# MCU.net
KiCad netlist of a schematic drawn in Altium Designer
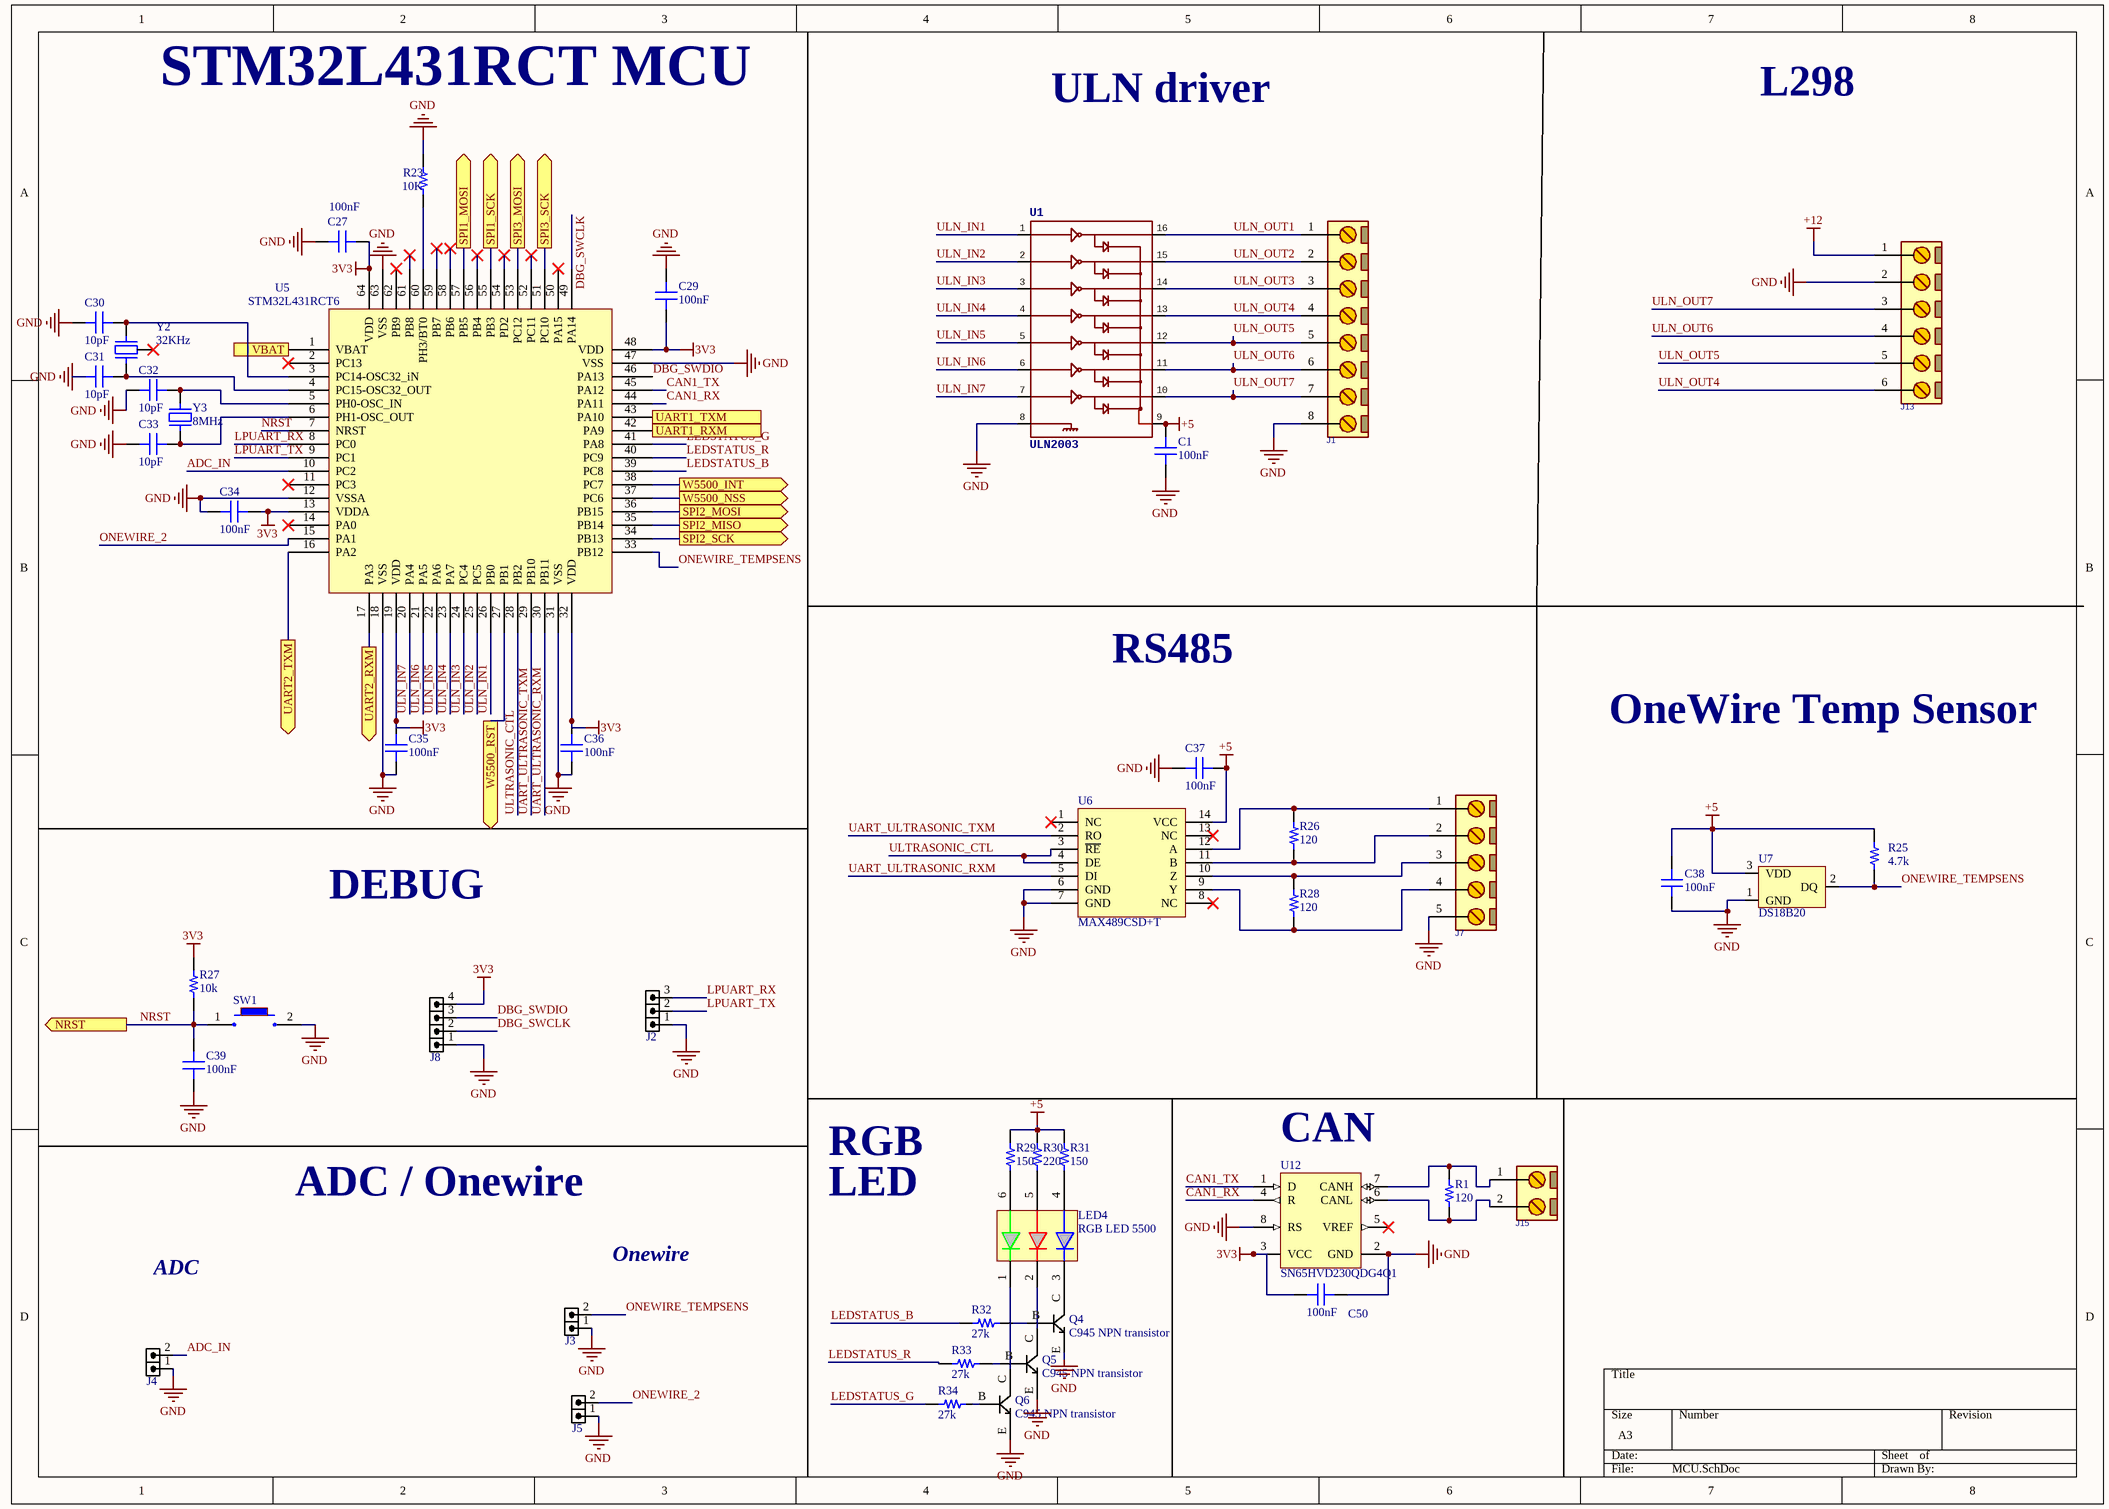
[diagram p0: MCU.SchDoc]

(export (version "E")
  (design (tool "Eeschema 10.0.6"))
  (components
    (comp (ref "C1")
      (value "100nF")
      (footprint "CAP 0805_2012")
      (description "SMT Capacitor")
      (libsource (lib "Capacitor") (part "Cap 0805"))
    )
    (comp (ref "C27")
      (value "100nF")
      (footprint "CAP 0805_2012")
      (description "SMT Capacitor")
      (libsource (lib "Capacitor") (part "Cap 0805"))
    )
    (comp (ref "C29")
      (value "100nF")
      (footprint "CAP 0805_2012")
      (description "SMT Capacitor")
      (libsource (lib "Capacitor") (part "Cap 0805"))
    )
    (comp (ref "C30")
      (value "10pF")
      (footprint "CAP 0805_2012")
      (description "SMT Capacitor")
      (libsource (lib "Capacitor") (part "Cap 0805"))
    )
    (comp (ref "C31")
      (value "10pF")
      (footprint "CAP 0805_2012")
      (description "SMT Capacitor")
      (libsource (lib "Capacitor") (part "Cap 0805"))
    )
    (comp (ref "C32")
      (value "10pF")
      (footprint "CAP 0805_2012")
      (description "SMT Capacitor")
      (libsource (lib "Capacitor") (part "Cap 0805"))
    )
    (comp (ref "C33")
      (value "10pF")
      (footprint "CAP 0805_2012")
      (description "SMT Capacitor")
      (libsource (lib "Capacitor") (part "Cap 0805"))
    )
    (comp (ref "C34")
      (value "100nF")
      (footprint "CAP 0805_2012")
      (description "SMT Capacitor")
      (libsource (lib "Capacitor") (part "Cap 0805"))
    )
    (comp (ref "C35")
      (value "100nF")
      (footprint "CAP 0805_2012")
      (description "SMT Capacitor")
      (libsource (lib "Capacitor") (part "Cap 0805"))
    )
    (comp (ref "C36")
      (value "100nF")
      (footprint "CAP 0805_2012")
      (description "SMT Capacitor")
      (libsource (lib "Capacitor") (part "Cap 0805"))
    )
    (comp (ref "C37")
      (value "100nF")
      (footprint "CAP 0805_2012")
      (description "SMT Capacitor")
      (libsource (lib "Capacitor") (part "Cap 0805"))
    )
    (comp (ref "C38")
      (value "100nF")
      (footprint "CAP 0805_2012")
      (description "SMT Capacitor")
      (libsource (lib "Capacitor") (part "Cap 0805"))
    )
    (comp (ref "C39")
      (value "100nF")
      (footprint "CAP 0805_2012")
      (description "SMT Capacitor")
      (libsource (lib "Capacitor") (part "Cap 0805"))
    )
    (comp (ref "C50")
      (value "100nF")
      (footprint "CAP 0805_2012")
      (description "SMT Capacitor")
      (libsource (lib "Capacitor") (part "Cap 0805"))
    )
    (comp (ref "J1")
      (value "Phoenix MSTBV 8Pin")
      (footprint "PHOENIX MSTBV_8")
      (description "CONN, PHOENIX MSTBV, 5-G, 5.08mm pitch")
      (fields (field (name "PARTNUMBER") "MSTBV 2,5/ 8-G-5,08 1758076"))
      (libsource (lib "Conn Terminal") (part "Phoenix MSTBV 8Pin"))
    )
    (comp (ref "J2")
      (value "HDRM3")
      (footprint "HDR_M_1X3")
      (description "CONN, HEADER, Male, pitch: 2.54mm, 3POS")
      (libsource (lib "Conn Header") (part "HDR_M_1X3"))
    )
    (comp (ref "J3")
      (value "HDRM2")
      (footprint "HDR_M_1X2")
      (description "CONN, HEADER, Male, pitch: 2.54mm, 2POS")
      (libsource (lib "Conn Header") (part "HDR_M_1X2"))
    )
    (comp (ref "J4")
      (value "HDRM2")
      (footprint "HDR_M_1X2")
      (description "CONN, HEADER, Male, pitch: 2.54mm, 2POS")
      (libsource (lib "Conn Header") (part "HDR_M_1X2"))
    )
    (comp (ref "J5")
      (value "HDRM2")
      (footprint "HDR_M_1X2")
      (description "CONN, HEADER, Male, pitch: 2.54mm, 2POS")
      (libsource (lib "Conn Header") (part "HDR_M_1X2"))
    )
    (comp (ref "J7")
      (value "Phoenix MSTBV 5Pin")
      (footprint "PHOENIX MSTBV_5")
      (description "CONN, PHOENIX MSTBV, 5-G, 5.08mm pitch")
      (fields (field (name "PARTNUMBER") "MSTBV 2,5/ 5-G-5,08 1758047"))
      (libsource (lib "Conn Terminal") (part "Phoenix MSTBV 5Pin"))
    )
    (comp (ref "J8")
      (value "HDR1X4")
      (footprint "HDR_M_1X4")
      (description "CONN, HEADER, Male, pitch: 2.54mm, 4POS")
      (libsource (lib "Conn Header") (part "HDR_M_1X4"))
    )
    (comp (ref "J13")
      (value "Phoenix MKDS 6Pin")
      (footprint "TBG_6")
      (description "CONN, PHOENIX MKDS, 5.08mm pitch")
      (fields (field (name "PARTNUMBER") "MKDS 1,5/ 6-5,08 - 1710726"))
      (libsource (lib "Conn Terminal") (part "Phoenix MKDS 6Pin"))
    )
    (comp (ref "J15")
      (value "Phoenix MSTBV 2Pin")
      (footprint "PHOENIX MSTBV_2")
      (description "CONN, PHOENIX MSTBV, 5-G, 5.08mm pitch")
      (fields (field (name "PARTNUMBER") "MSTBV 2,5/ 2-G-5,08 - 1758018"))
      (libsource (lib "Conn Terminal") (part "Phoenix MSTBV 2Pin"))
    )
    (comp (ref "LED4")
      (value "RGB LED 5500")
      (footprint "LED5500")
      (libsource (lib "AlTaLibs_MCU") (part "LED RGB 5500 Common Anode"))
    )
    (comp (ref "Q4")
      (value "C945 NPN transistor")
      (footprint "SO-23")
      (description "C945 NPN transistor hfE = 140~400")
      (libsource (lib "AlTaLibs") (part "C945"))
    )
    (comp (ref "Q5")
      (value "C945 NPN transistor")
      (footprint "SO-23")
      (description "C945 NPN transistor hfE = 140~400")
      (libsource (lib "AlTaLibs") (part "C945"))
    )
    (comp (ref "Q6")
      (value "C945 NPN transistor")
      (footprint "SO-23")
      (description "C945 NPN transistor hfE = 140~400")
      (libsource (lib "AlTaLibs") (part "C945"))
    )
    (comp (ref "R1")
      (value "120")
      (footprint "RES 0805_2012")
      (description "SMT Resistor")
      (libsource (lib "Resistor") (part "Res 0805"))
    )
    (comp (ref "R23")
      (value "10K")
      (footprint "RES 0805_2012")
      (description "SMT Resistor")
      (libsource (lib "Resistor") (part "Res 0805"))
    )
    (comp (ref "R25")
      (value "4.7k")
      (footprint "RES 0805_2012")
      (description "SMT Resistor")
      (libsource (lib "Resistor") (part "Res 0805"))
    )
    (comp (ref "R26")
      (value "120")
      (footprint "RES 0805_2012")
      (description "SMT Resistor")
      (libsource (lib "Resistor") (part "Res 0805"))
    )
    (comp (ref "R27")
      (value "10k")
      (footprint "RES 0805_2012")
      (description "SMT Resistor")
      (libsource (lib "Resistor") (part "Res 0805"))
    )
    (comp (ref "R28")
      (value "120")
      (footprint "RES 0805_2012")
      (description "SMT Resistor")
      (libsource (lib "Resistor") (part "Res 0805"))
    )
    (comp (ref "R29")
      (value "150")
      (footprint "RES 0805_2012")
      (description "SMT Resistor")
      (libsource (lib "Resistor") (part "Res 0805"))
    )
    (comp (ref "R30")
      (value "220")
      (footprint "RES 0805_2012")
      (description "SMT Resistor")
      (libsource (lib "Resistor") (part "Res 0805"))
    )
    (comp (ref "R31")
      (value "150")
      (footprint "RES 0805_2012")
      (description "SMT Resistor")
      (libsource (lib "Resistor") (part "Res 0805"))
    )
    (comp (ref "R32")
      (value "27k")
      (footprint "RES 0805_2012")
      (description "SMT Resistor")
      (libsource (lib "Resistor") (part "Res 0805"))
    )
    (comp (ref "R33")
      (value "27k")
      (footprint "RES 0805_2012")
      (description "SMT Resistor")
      (libsource (lib "Resistor") (part "Res 0805"))
    )
    (comp (ref "R34")
      (value "27k")
      (footprint "RES 0805_2012")
      (description "SMT Resistor")
      (libsource (lib "Resistor") (part "Res 0805"))
    )
    (comp (ref "SW1")
      (value "Rec. Button")
      (footprint "REC_PUSHBUTTON_FTPRNT")
      (libsource (lib "AlTaLibs") (part "Rectangle_PushButton"))
    )
    (comp (ref "U1")
      (value "ULN2003")
      (footprint "SOIC-16 9.9X3.9MM P1.27MM")
      (description "Bipolar (BJT) Transistor Array 7 NPN Darlington 50V 500mA   Surface Mount 16-SO")
      (fields (field (name "PARTNUMBER") "ULN2003D1013TR"))
      (libsource (lib "Chip") (part "ULN2003 (SMD)"))
    )
    (comp (ref "U5")
      (value "STM32L431RCT6")
      (footprint "LQFP64")
      (description "IC MCU 32BIT 256KB FLASH 64LQFP")
      (fields (field (name "MANUFACTURER") "STMicroelectronics"))
      (libsource (lib "AlTaLibs") (part "STM32L431RCT6"))
    )
    (comp (ref "U6")
      (value "MAX489CSD+T")
      (footprint "SOIC-14")
      (description "MAX489 Series 0.25 Mbps 12V Full Duplex SMT RS 485 Transceiver - SOIC-14")
      (fields (field (name "MANUFACTURER") "Maxim"))
      (libsource (lib "AlTaLibs") (part "MAX489CSD+T"))
    )
    (comp (ref "U7")
      (value "DS18B20")
      (footprint "TO-92A")
      (description "Temperature Sensor Digital, Local -55°C ~ 125°C 12 b TO-92-3")
      (fields (field (name "PARTNUMBER") "DS18B20+T&R"))
      (libsource (lib "Chip") (part "DS18B20 (THD)"))
    )
    (comp (ref "U12")
      (value "SN65HVD230QDG4Q1")
      (footprint "D8_L")
      (fields (field (name "MANUFACTURER") "Texas Instruments"))
      (libsource (lib "Texas Instruments Interface CAN") (part "SN65HVD230QDG4Q1"))
    )
    (comp (ref "Y2")
      (value "32KHz")
      (footprint "C-002R TH")
      (description "SMT Crystal")
      (libsource (lib "Xtal") (part "Crystal C-002R THD"))
    )
    (comp (ref "Y3")
      (value "8MHz")
      (footprint "HC-49S SMD")
      (description "SMT Crystal")
      (fields (field (name "PARTNUMBER") "ABLS-8.000MHZ-K4T"))
      (libsource (lib "Xtal") (part "Crystal HC-49S SMD 8MHz"))
    )
  )
  (nets
    (net (code "1") (name "+5") (class "Default")
      (node (ref "C1") (pin "2") (pinfunction "2_2") (pintype "passive"))
      (node (ref "C37") (pin "2") (pinfunction "2_2") (pintype "passive"))
      (node (ref "C38") (pin "2") (pinfunction "2_2") (pintype "passive"))
      (node (ref "R25") (pin "1") (pinfunction "1_1") (pintype "passive"))
      (node (ref "R29") (pin "2") (pinfunction "2_2") (pintype "passive"))
      (node (ref "R30") (pin "2") (pinfunction "2_2") (pintype "passive"))
      (node (ref "R31") (pin "2") (pinfunction "2_2") (pintype "passive"))
      (node (ref "U1") (pin "9") (pinfunction "9_9") (pintype "passive"))
      (node (ref "U6") (pin "14") (pinfunction "VCC_14") (pintype "passive"))
      (node (ref "U7") (pin "3") (pinfunction "VDD_3") (pintype "passive"))
    )
    (net (code "2") (name "+12") (class "Default")
      (node (ref "J13") (pin "1") (pinfunction "1_1") (pintype "passive"))
    )
    (net (code "3") (name "/ADC_IN") (class "Default")
      (node (ref "J4") (pin "2") (pinfunction "2_2") (pintype "passive"))
      (node (ref "U5") (pin "10") (pinfunction "PC2_10") (pintype "passive"))
    )
    (net (code "4") (name "/CAN1_RX") (class "Default")
      (node (ref "U12") (pin "4") (pinfunction "R_4") (pintype "output"))
      (node (ref "U5") (pin "44") (pinfunction "PA11_44") (pintype "passive"))
    )
    (net (code "5") (name "/CAN1_TX") (class "Default")
      (node (ref "U12") (pin "1") (pinfunction "D_1") (pintype "input"))
      (node (ref "U5") (pin "45") (pinfunction "PA12_45") (pintype "passive"))
    )
    (net (code "6") (name "/DBG_SWCLK") (class "Default")
      (node (ref "J8") (pin "2") (pinfunction "2_2") (pintype "passive"))
      (node (ref "U5") (pin "49") (pinfunction "PA14_49") (pintype "passive"))
    )
    (net (code "7") (name "/DBG_SWDIO") (class "Default")
      (node (ref "J8") (pin "3") (pinfunction "3_3") (pintype "passive"))
      (node (ref "U5") (pin "46") (pinfunction "PA13_46") (pintype "passive"))
    )
    (net (code "8") (name "/LEDSTATUS_B") (class "Default")
      (node (ref "R32") (pin "1") (pinfunction "1_1") (pintype "passive"))
      (node (ref "U5") (pin "39") (pinfunction "PC8_39") (pintype "passive"))
    )
    (net (code "9") (name "/LEDSTATUS_G") (class "Default")
      (node (ref "R34") (pin "1") (pinfunction "1_1") (pintype "passive"))
      (node (ref "U5") (pin "41") (pinfunction "PA8_41") (pintype "passive"))
    )
    (net (code "10") (name "/LEDSTATUS_R") (class "Default")
      (node (ref "R33") (pin "1") (pinfunction "1_1") (pintype "passive"))
      (node (ref "U5") (pin "40") (pinfunction "PC9_40") (pintype "passive"))
    )
    (net (code "11") (name "/LPUART_RX") (class "Default")
      (node (ref "J2") (pin "3") (pinfunction "3_3") (pintype "passive"))
      (node (ref "U5") (pin "8") (pinfunction "PC0_8") (pintype "passive"))
    )
    (net (code "12") (name "/LPUART_TX") (class "Default")
      (node (ref "J2") (pin "2") (pinfunction "2_2") (pintype "passive"))
      (node (ref "U5") (pin "9") (pinfunction "PC1_9") (pintype "passive"))
    )
    (net (code "13") (name "/NRST") (class "Default")
      (node (ref "C39") (pin "2") (pinfunction "2_2") (pintype "passive"))
      (node (ref "R27") (pin "1") (pinfunction "1_1") (pintype "passive"))
      (node (ref "SW1") (pin "1") (pintype "passive"))
      (node (ref "U5") (pin "7") (pinfunction "NRST_7") (pintype "passive"))
    )
    (net (code "14") (name "/ONEWIRE_2") (class "Default")
      (node (ref "J5") (pin "2") (pinfunction "2_2") (pintype "passive"))
      (node (ref "U5") (pin "15") (pinfunction "PA1_15") (pintype "passive"))
    )
    (net (code "15") (name "/ONEWIRE_TEMPSENS") (class "Default")
      (node (ref "J3") (pin "2") (pinfunction "2_2") (pintype "passive"))
      (node (ref "R25") (pin "2") (pinfunction "2_2") (pintype "passive"))
      (node (ref "U5") (pin "33") (pinfunction "PB12_33") (pintype "passive"))
      (node (ref "U7") (pin "2") (pinfunction "DQ_2") (pintype "passive"))
    )
    (net (code "16") (name "/SPI1_MOSI") (class "Default")
      (node (ref "U5") (pin "57") (pinfunction "PB5_57") (pintype "passive"))
    )
    (net (code "17") (name "/SPI1_SCK") (class "Default")
      (node (ref "U5") (pin "55") (pinfunction "PB3_55") (pintype "passive"))
    )
    (net (code "18") (name "/SPI2_MISO") (class "Default")
      (node (ref "U5") (pin "35") (pinfunction "PB14_35") (pintype "passive"))
    )
    (net (code "19") (name "/SPI2_MOSI") (class "Default")
      (node (ref "U5") (pin "36") (pinfunction "PB15_36") (pintype "passive"))
    )
    (net (code "20") (name "/SPI2_SCK") (class "Default")
      (node (ref "U5") (pin "34") (pinfunction "PB13_34") (pintype "passive"))
    )
    (net (code "21") (name "/SPI3_MOSI") (class "Default")
      (node (ref "U5") (pin "53") (pinfunction "PC12_53") (pintype "passive"))
    )
    (net (code "22") (name "/SPI3_SCK") (class "Default")
      (node (ref "U5") (pin "51") (pinfunction "PC10_51") (pintype "passive"))
    )
    (net (code "23") (name "/UART1_RXM") (class "Default")
      (node (ref "U5") (pin "42") (pinfunction "PA9_42") (pintype "passive"))
    )
    (net (code "24") (name "/UART1_TXM") (class "Default")
      (node (ref "U5") (pin "43") (pinfunction "PA10_43") (pintype "passive"))
    )
    (net (code "25") (name "/UART2_RXM") (class "Default")
      (node (ref "U5") (pin "17") (pinfunction "PA3_17") (pintype "passive"))
    )
    (net (code "26") (name "/UART2_TXM") (class "Default")
      (node (ref "U5") (pin "16") (pinfunction "PA2_16") (pintype "passive"))
    )
    (net (code "27") (name "/UART_ULTRASONIC_RXM") (class "Default")
      (node (ref "U5") (pin "30") (pinfunction "PB11_30") (pintype "passive"))
      (node (ref "U6") (pin "5") (pinfunction "DI_5") (pintype "passive"))
    )
    (net (code "28") (name "/UART_ULTRASONIC_TXM") (class "Default")
      (node (ref "U5") (pin "29") (pinfunction "PB10_29") (pintype "passive"))
      (node (ref "U6") (pin "2") (pinfunction "RO_2") (pintype "passive"))
    )
    (net (code "29") (name "/ULN_IN1") (class "Default")
      (node (ref "U1") (pin "1") (pinfunction "1_1") (pintype "passive"))
      (node (ref "U5") (pin "26") (pinfunction "PB0_26") (pintype "passive"))
    )
    (net (code "30") (name "/ULN_IN2") (class "Default")
      (node (ref "U1") (pin "2") (pinfunction "2_2") (pintype "passive"))
      (node (ref "U5") (pin "25") (pinfunction "PC5_25") (pintype "passive"))
    )
    (net (code "31") (name "/ULN_IN3") (class "Default")
      (node (ref "U1") (pin "3") (pinfunction "3_3") (pintype "passive"))
      (node (ref "U5") (pin "24") (pinfunction "PC4_24") (pintype "passive"))
    )
    (net (code "32") (name "/ULN_IN4") (class "Default")
      (node (ref "U1") (pin "4") (pinfunction "4_4") (pintype "passive"))
      (node (ref "U5") (pin "23") (pinfunction "PA7_23") (pintype "passive"))
    )
    (net (code "33") (name "/ULN_IN5") (class "Default")
      (node (ref "U1") (pin "5") (pinfunction "5_5") (pintype "passive"))
      (node (ref "U5") (pin "22") (pinfunction "PA6_22") (pintype "passive"))
    )
    (net (code "34") (name "/ULN_IN6") (class "Default")
      (node (ref "U1") (pin "6") (pinfunction "6_6") (pintype "passive"))
      (node (ref "U5") (pin "21") (pinfunction "PA5_21") (pintype "passive"))
    )
    (net (code "35") (name "/ULN_IN7") (class "Default")
      (node (ref "U1") (pin "7") (pinfunction "7_7") (pintype "passive"))
      (node (ref "U5") (pin "20") (pinfunction "PA4_20") (pintype "passive"))
    )
    (net (code "36") (name "/ULN_OUT1") (class "Default")
      (node (ref "J1") (pin "1") (pinfunction "1_1") (pintype "passive"))
      (node (ref "U1") (pin "16") (pinfunction "16_16") (pintype "passive"))
    )
    (net (code "37") (name "/ULN_OUT2") (class "Default")
      (node (ref "J1") (pin "2") (pinfunction "2_2") (pintype "passive"))
      (node (ref "U1") (pin "15") (pinfunction "15_15") (pintype "passive"))
    )
    (net (code "38") (name "/ULN_OUT3") (class "Default")
      (node (ref "J1") (pin "3") (pinfunction "3_3") (pintype "passive"))
      (node (ref "U1") (pin "14") (pinfunction "14_14") (pintype "passive"))
    )
    (net (code "39") (name "/ULN_OUT4") (class "Default")
      (node (ref "J1") (pin "4") (pinfunction "4_4") (pintype "passive"))
      (node (ref "J13") (pin "6") (pinfunction "6_6") (pintype "passive"))
      (node (ref "U1") (pin "13") (pinfunction "13_13") (pintype "passive"))
    )
    (net (code "40") (name "/ULN_OUT5") (class "Default")
      (node (ref "J1") (pin "5") (pinfunction "5_5") (pintype "passive"))
      (node (ref "J13") (pin "5") (pinfunction "5_5") (pintype "passive"))
      (node (ref "U1") (pin "12") (pinfunction "12_12") (pintype "passive"))
    )
    (net (code "41") (name "/ULN_OUT6") (class "Default")
      (node (ref "J1") (pin "6") (pinfunction "6_6") (pintype "passive"))
      (node (ref "J13") (pin "4") (pinfunction "4_4") (pintype "passive"))
      (node (ref "U1") (pin "11") (pinfunction "11_11") (pintype "passive"))
    )
    (net (code "42") (name "/ULN_OUT7") (class "Default")
      (node (ref "J1") (pin "7") (pinfunction "7_7") (pintype "passive"))
      (node (ref "J13") (pin "3") (pinfunction "3_3") (pintype "passive"))
      (node (ref "U1") (pin "10") (pinfunction "10_10") (pintype "passive"))
    )
    (net (code "43") (name "/ULTRASONIC_CTL") (class "Default")
      (node (ref "U5") (pin "28") (pinfunction "PB2_28") (pintype "passive"))
      (node (ref "U6") (pin "3") (pinfunction "~{RE}_3") (pintype "passive"))
      (node (ref "U6") (pin "4") (pinfunction "DE_4") (pintype "passive"))
    )
    (net (code "44") (name "/VBAT") (class "Default")
      (node (ref "U5") (pin "1") (pinfunction "VBAT_1") (pintype "passive"))
    )
    (net (code "45") (name "/W5500_INT") (class "Default")
      (node (ref "U5") (pin "38") (pinfunction "PC7_38") (pintype "passive"))
    )
    (net (code "46") (name "/W5500_NSS") (class "Default")
      (node (ref "U5") (pin "37") (pinfunction "PC6_37") (pintype "passive"))
    )
    (net (code "47") (name "/W5500_RST") (class "Default")
      (node (ref "U5") (pin "27") (pinfunction "PB1_27") (pintype "passive"))
    )
    (net (code "48") (name "3V3") (class "Default")
      (node (ref "C27") (pin "1") (pinfunction "1_1") (pintype "passive"))
      (node (ref "C29") (pin "1") (pinfunction "1_1") (pintype "passive"))
      (node (ref "C34") (pin "2") (pinfunction "2_2") (pintype "passive"))
      (node (ref "C35") (pin "2") (pinfunction "2_2") (pintype "passive"))
      (node (ref "C36") (pin "2") (pinfunction "2_2") (pintype "passive"))
      (node (ref "C50") (pin "2") (pinfunction "2_2") (pintype "passive"))
      (node (ref "J8") (pin "4") (pinfunction "4_4") (pintype "passive"))
      (node (ref "R27") (pin "2") (pinfunction "2_2") (pintype "passive"))
      (node (ref "U12") (pin "3") (pinfunction "VCC_3") (pintype "power_in"))
      (node (ref "U5") (pin "13") (pinfunction "VDDA_13") (pintype "passive"))
      (node (ref "U5") (pin "19") (pinfunction "VDD_19") (pintype "passive"))
      (node (ref "U5") (pin "32") (pinfunction "VDD_32") (pintype "passive"))
      (node (ref "U5") (pin "48") (pinfunction "VDD_48") (pintype "passive"))
      (node (ref "U5") (pin "64") (pinfunction "VDD_64") (pintype "passive"))
    )
    (net (code "49") (name "GND") (class "Default")
      (node (ref "C1") (pin "1") (pinfunction "1_1") (pintype "passive"))
      (node (ref "C27") (pin "2") (pinfunction "2_2") (pintype "passive"))
      (node (ref "C29") (pin "2") (pinfunction "2_2") (pintype "passive"))
      (node (ref "C30") (pin "1") (pinfunction "1_1") (pintype "passive"))
      (node (ref "C31") (pin "1") (pinfunction "1_1") (pintype "passive"))
      (node (ref "C32") (pin "1") (pinfunction "1_1") (pintype "passive"))
      (node (ref "C33") (pin "1") (pinfunction "1_1") (pintype "passive"))
      (node (ref "C34") (pin "1") (pinfunction "1_1") (pintype "passive"))
      (node (ref "C35") (pin "1") (pinfunction "1_1") (pintype "passive"))
      (node (ref "C36") (pin "1") (pinfunction "1_1") (pintype "passive"))
      (node (ref "C37") (pin "1") (pinfunction "1_1") (pintype "passive"))
      (node (ref "C38") (pin "1") (pinfunction "1_1") (pintype "passive"))
      (node (ref "C39") (pin "1") (pinfunction "1_1") (pintype "passive"))
      (node (ref "C50") (pin "1") (pinfunction "1_1") (pintype "passive"))
      (node (ref "J1") (pin "8") (pinfunction "8_8") (pintype "passive"))
      (node (ref "J13") (pin "2") (pinfunction "2_2") (pintype "passive"))
      (node (ref "J2") (pin "1") (pinfunction "1_1") (pintype "passive"))
      (node (ref "J3") (pin "1") (pinfunction "1_1") (pintype "passive"))
      (node (ref "J4") (pin "1") (pinfunction "1_1") (pintype "passive"))
      (node (ref "J5") (pin "1") (pinfunction "1_1") (pintype "passive"))
      (node (ref "J7") (pin "5") (pinfunction "5_5") (pintype "passive"))
      (node (ref "J8") (pin "1") (pinfunction "1_1") (pintype "passive"))
      (node (ref "Q4") (pin "E") (pintype "passive"))
      (node (ref "Q5") (pin "E") (pintype "passive"))
      (node (ref "Q6") (pin "E") (pintype "passive"))
      (node (ref "R23") (pin "1") (pinfunction "1_1") (pintype "passive"))
      (node (ref "SW1") (pin "2") (pintype "passive"))
      (node (ref "U1") (pin "8") (pinfunction "8_8") (pintype "passive"))
      (node (ref "U12") (pin "2") (pinfunction "GND_2") (pintype "power_in"))
      (node (ref "U12") (pin "8") (pinfunction "RS_8") (pintype "input"))
      (node (ref "U5") (pin "12") (pinfunction "VSSA_12") (pintype "passive"))
      (node (ref "U5") (pin "18") (pinfunction "VSS_18") (pintype "passive"))
      (node (ref "U5") (pin "31") (pinfunction "VSS_31") (pintype "passive"))
      (node (ref "U5") (pin "47") (pinfunction "VSS_47") (pintype "passive"))
      (node (ref "U5") (pin "63") (pinfunction "VSS_63") (pintype "passive"))
      (node (ref "U6") (pin "6") (pinfunction "GND_6") (pintype "passive"))
      (node (ref "U6") (pin "7") (pinfunction "GND_7") (pintype "passive"))
      (node (ref "U7") (pin "1") (pinfunction "GND_1") (pintype "passive"))
    )
    (net (code "50") (name "Net-(LED4-Pad1)") (class "Default")
      (node (ref "LED4") (pin "1") (pintype "passive"))
      (node (ref "Q6") (pin "C") (pintype "passive"))
    )
    (net (code "51") (name "Net-(LED4-Pad2)") (class "Default")
      (node (ref "LED4") (pin "2") (pintype "passive"))
      (node (ref "Q5") (pin "C") (pintype "passive"))
    )
    (net (code "52") (name "Net-(LED4-Pad3)") (class "Default")
      (node (ref "LED4") (pin "3") (pintype "passive"))
      (node (ref "Q4") (pin "C") (pintype "passive"))
    )
    (net (code "53") (name "Net-(LED4-Pad4)") (class "Default")
      (node (ref "LED4") (pin "4") (pintype "passive"))
      (node (ref "R31") (pin "1") (pinfunction "1_1") (pintype "passive"))
    )
    (net (code "54") (name "Net-(LED4-Pad5)") (class "Default")
      (node (ref "LED4") (pin "5") (pintype "passive"))
      (node (ref "R30") (pin "1") (pinfunction "1_1") (pintype "passive"))
    )
    (net (code "55") (name "Net-(LED4-Pad6)") (class "Default")
      (node (ref "LED4") (pin "6") (pintype "passive"))
      (node (ref "R29") (pin "1") (pinfunction "1_1") (pintype "passive"))
    )
    (net (code "56") (name "Net-(Q4-PadB)") (class "Default")
      (node (ref "Q4") (pin "B") (pintype "passive"))
      (node (ref "R32") (pin "2") (pinfunction "2_2") (pintype "passive"))
    )
    (net (code "57") (name "Net-(Q5-PadB)") (class "Default")
      (node (ref "Q5") (pin "B") (pintype "passive"))
      (node (ref "R33") (pin "2") (pinfunction "2_2") (pintype "passive"))
    )
    (net (code "58") (name "Net-(Q6-PadB)") (class "Default")
      (node (ref "Q6") (pin "B") (pintype "passive"))
      (node (ref "R34") (pin "2") (pinfunction "2_2") (pintype "passive"))
    )
    (net (code "59") (name "Net-(U5-PC14-OSC32_iN)") (class "Default")
      (node (ref "C30") (pin "2") (pinfunction "2_2") (pintype "passive"))
      (node (ref "U5") (pin "3") (pinfunction "PC14-OSC32_iN_3") (pintype "passive"))
      (node (ref "Y2") (pin "2") (pinfunction "2_2") (pintype "passive"))
    )
    (net (code "60") (name "Net-(U5-PC15-OSC32_OUT)") (class "Default")
      (node (ref "C31") (pin "2") (pinfunction "2_2") (pintype "passive"))
      (node (ref "U5") (pin "4") (pinfunction "PC15-OSC32_OUT_4") (pintype "passive"))
      (node (ref "Y2") (pin "1") (pinfunction "1_1") (pintype "passive"))
    )
    (net (code "61") (name "Net-(U5-PH0-OSC_IN)") (class "Default")
      (node (ref "C32") (pin "2") (pinfunction "2_2") (pintype "passive"))
      (node (ref "U5") (pin "5") (pinfunction "PH0-OSC_IN_5") (pintype "passive"))
      (node (ref "Y3") (pin "2") (pinfunction "2_2") (pintype "passive"))
    )
    (net (code "62") (name "Net-(U5-PH1-OSC_OUT)") (class "Default")
      (node (ref "C33") (pin "2") (pinfunction "2_2") (pintype "passive"))
      (node (ref "U5") (pin "6") (pinfunction "PH1-OSC_OUT_6") (pintype "passive"))
      (node (ref "Y3") (pin "1") (pinfunction "1_1") (pintype "passive"))
    )
    (net (code "63") (name "Net-(U5-PH3{slash}BT0)") (class "Default")
      (node (ref "R23") (pin "2") (pinfunction "2_2") (pintype "passive"))
      (node (ref "U5") (pin "60") (pinfunction "PH3/BT0_60") (pintype "passive"))
    )
    (net (code "64") (name "Net-(U6-A)") (class "Default")
      (node (ref "J7") (pin "1") (pinfunction "1_1") (pintype "passive"))
      (node (ref "R26") (pin "2") (pinfunction "2_2") (pintype "passive"))
      (node (ref "U6") (pin "12") (pinfunction "A_12") (pintype "passive"))
    )
    (net (code "65") (name "Net-(U6-B)") (class "Default")
      (node (ref "J7") (pin "2") (pinfunction "2_2") (pintype "passive"))
      (node (ref "R26") (pin "1") (pinfunction "1_1") (pintype "passive"))
      (node (ref "U6") (pin "11") (pinfunction "B_11") (pintype "passive"))
    )
    (net (code "66") (name "Net-(U6-Y)") (class "Default")
      (node (ref "J7") (pin "4") (pinfunction "4_4") (pintype "passive"))
      (node (ref "R28") (pin "1") (pinfunction "1_1") (pintype "passive"))
      (node (ref "U6") (pin "9") (pinfunction "Y_9") (pintype "passive"))
    )
    (net (code "67") (name "Net-(U6-Z)") (class "Default")
      (node (ref "J7") (pin "3") (pinfunction "3_3") (pintype "passive"))
      (node (ref "R28") (pin "2") (pinfunction "2_2") (pintype "passive"))
      (node (ref "U6") (pin "10") (pinfunction "Z_10") (pintype "passive"))
    )
    (net (code "68") (name "Net-(U12-CANH)") (class "Default")
      (node (ref "J15") (pin "1") (pinfunction "1_1") (pintype "passive"))
      (node (ref "R1") (pin "2") (pinfunction "2_2") (pintype "passive"))
      (node (ref "U12") (pin "7") (pinfunction "CANH_7") (pintype "bidirectional"))
    )
    (net (code "69") (name "Net-(U12-CANL)") (class "Default")
      (node (ref "J15") (pin "2") (pinfunction "2_2") (pintype "passive"))
      (node (ref "R1") (pin "1") (pinfunction "1_1") (pintype "passive"))
      (node (ref "U12") (pin "6") (pinfunction "CANL_6") (pintype "bidirectional"))
    )
    (net (code "70") (name "unconnected-(U5-PA0-Pad14)") (class "Default")
      (node (ref "U5") (pin "14") (pinfunction "PA0_14") (pintype "passive+no_connect"))
    )
    (net (code "71") (name "unconnected-(U5-PA15-Pad50)") (class "Default")
      (node (ref "U5") (pin "50") (pinfunction "PA15_50") (pintype "passive+no_connect"))
    )
    (net (code "72") (name "unconnected-(U5-PB4-Pad56)") (class "Default")
      (node (ref "U5") (pin "56") (pinfunction "PB4_56") (pintype "passive+no_connect"))
    )
    (net (code "73") (name "unconnected-(U5-PB6-Pad58)") (class "Default")
      (node (ref "U5") (pin "58") (pinfunction "PB6_58") (pintype "passive+no_connect"))
    )
    (net (code "74") (name "unconnected-(U5-PB7-Pad59)") (class "Default")
      (node (ref "U5") (pin "59") (pinfunction "PB7_59") (pintype "passive+no_connect"))
    )
    (net (code "75") (name "unconnected-(U5-PB8-Pad61)") (class "Default")
      (node (ref "U5") (pin "61") (pinfunction "PB8_61") (pintype "passive+no_connect"))
    )
    (net (code "76") (name "unconnected-(U5-PB9-Pad62)") (class "Default")
      (node (ref "U5") (pin "62") (pinfunction "PB9_62") (pintype "passive+no_connect"))
    )
    (net (code "77") (name "unconnected-(U5-PC3-Pad11)") (class "Default")
      (node (ref "U5") (pin "11") (pinfunction "PC3_11") (pintype "passive+no_connect"))
    )
    (net (code "78") (name "unconnected-(U5-PC11-Pad52)") (class "Default")
      (node (ref "U5") (pin "52") (pinfunction "PC11_52") (pintype "passive+no_connect"))
    )
    (net (code "79") (name "unconnected-(U5-PC13-Pad2)") (class "Default")
      (node (ref "U5") (pin "2") (pinfunction "PC13_2") (pintype "passive+no_connect"))
    )
    (net (code "80") (name "unconnected-(U5-PD2-Pad54)") (class "Default")
      (node (ref "U5") (pin "54") (pinfunction "PD2_54") (pintype "passive+no_connect"))
    )
    (net (code "81") (name "unconnected-(U6-NC-Pad1)") (class "Default")
      (node (ref "U6") (pin "1") (pinfunction "NC_1") (pintype "passive+no_connect"))
    )
    (net (code "82") (name "unconnected-(U6-NC-Pad8)") (class "Default")
      (node (ref "U6") (pin "8") (pinfunction "NC_8") (pintype "passive+no_connect"))
    )
    (net (code "83") (name "unconnected-(U6-NC-Pad13)") (class "Default")
      (node (ref "U6") (pin "13") (pinfunction "NC_13") (pintype "passive+no_connect"))
    )
    (net (code "84") (name "unconnected-(U12-VREF-Pad5)") (class "Default")
      (node (ref "U12") (pin "5") (pinfunction "VREF_5") (pintype "output+no_connect"))
    )
    (net (code "85") (name "unconnected-(Y2-GND-Pad3)") (class "Default")
      (node (ref "Y2") (pin "3") (pinfunction "GND_3") (pintype "passive+no_connect"))
    )
  )
)
